# oresatt-batteries.net
KiCad netlist of a schematic drawn in EAGLE
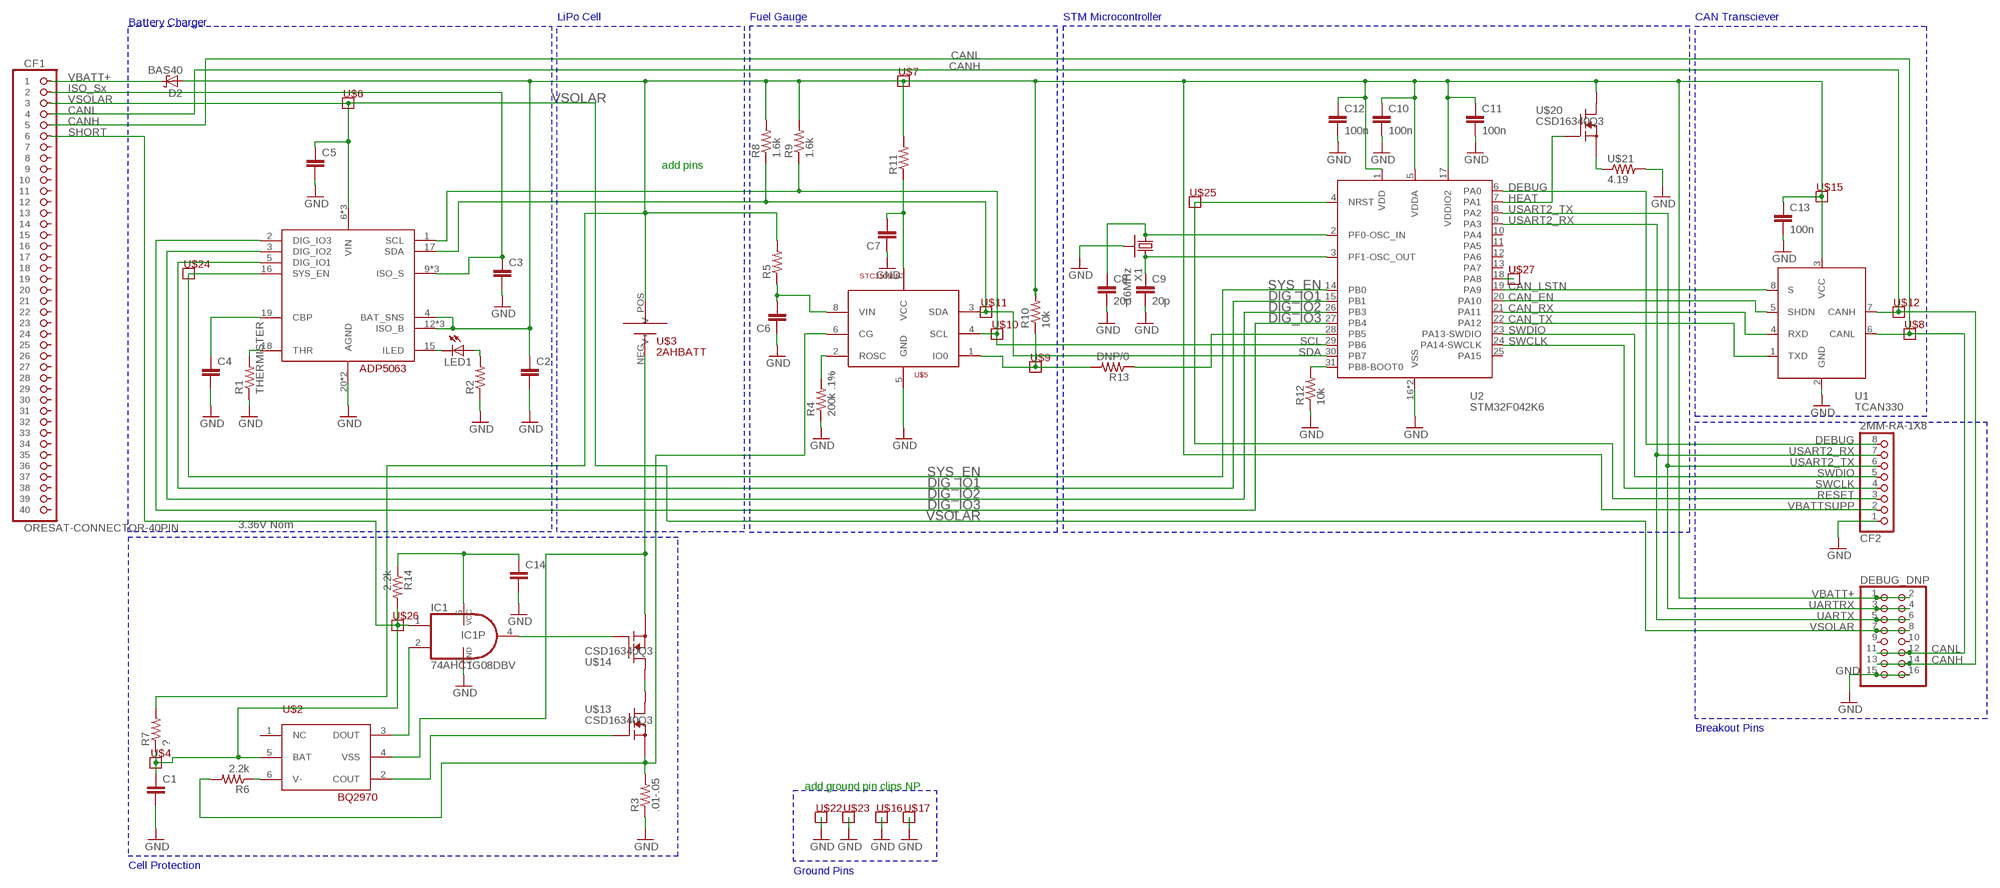
[diagram p0: schematic, sheet 1]

(export (version "E")
  (design (tool "Eeschema 10.0.6"))
  (components
    (comp (ref "C1")
      (value "C-EUC0603")
      (footprint "eagle-import:C0603")
      (libsource (lib "eagle-import") (part "C-EUC0603"))
    )
    (comp (ref "C2")
      (value "C-EUC0603")
      (footprint "eagle-import:C0603")
      (libsource (lib "eagle-import") (part "C-EUC0603"))
    )
    (comp (ref "C3")
      (value "C-EUC0603")
      (footprint "eagle-import:C0603")
      (libsource (lib "eagle-import") (part "C-EUC0603"))
    )
    (comp (ref "C4")
      (value "C-EUC0603")
      (footprint "eagle-import:C0603")
      (libsource (lib "eagle-import") (part "C-EUC0603"))
    )
    (comp (ref "C5")
      (value "C-EUC0603")
      (footprint "eagle-import:C0603")
      (libsource (lib "eagle-import") (part "C-EUC0603"))
    )
    (comp (ref "C6")
      (value "C-EUC0603")
      (footprint "eagle-import:C0603")
      (libsource (lib "eagle-import") (part "C-EUC0603"))
    )
    (comp (ref "C7")
      (value "C-EUC0603")
      (footprint "eagle-import:C0603")
      (libsource (lib "eagle-import") (part "C-EUC0603"))
    )
    (comp (ref "C8")
      (value "20p")
      (footprint "eagle-import:C0603")
      (libsource (lib "eagle-import") (part "C-EUC0603"))
    )
    (comp (ref "C9")
      (value "20p")
      (footprint "eagle-import:C0603")
      (libsource (lib "eagle-import") (part "C-EUC0603"))
    )
    (comp (ref "C10")
      (value "100n")
      (footprint "eagle-import:C0603")
      (libsource (lib "eagle-import") (part "C-EUC0603"))
    )
    (comp (ref "C11")
      (value "100n")
      (footprint "eagle-import:C0603")
      (libsource (lib "eagle-import") (part "C-EUC0603"))
    )
    (comp (ref "C12")
      (value "100n")
      (footprint "eagle-import:C0603")
      (libsource (lib "eagle-import") (part "C-EUC0603"))
    )
    (comp (ref "C13")
      (value "100n")
      (footprint "eagle-import:C0603")
      (libsource (lib "eagle-import") (part "C-EUC0603"))
    )
    (comp (ref "C14")
      (value "C-EUC0603")
      (footprint "eagle-import:C0603")
      (libsource (lib "eagle-import") (part "C-EUC0603"))
    )
    (comp (ref "CF1")
      (value "ORESAT-CONNECTOR-40PIN")
      (footprint "eagle-import:HARWIN-ARCHER-M50-3202045")
      (libsource (lib "eagle-import") (part "ORESAT-CONNECTOR-40PIN"))
    )
    (comp (ref "CF2")
      (value "2MM-RA-1X8")
      (footprint "eagle-import:CF-2MM-RA-1X8-PRECIDIP-831")
      (libsource (lib "eagle-import") (part "2MM-RA-1X8"))
    )
    (comp (ref "D2")
      (value "BAS40")
      (footprint "eagle-import:SOT23")
      (libsource (lib "eagle-import") (part "BAS40"))
    )
    (comp (ref "DEBUG_DNP")
      (value "PINHD-2X8")
      (footprint "eagle-import:2X08")
      (libsource (lib "eagle-import") (part "PINHD-2X8"))
    )
    (comp (ref "IC1")
      (value "74AHC1G08DBV")
      (footprint "eagle-import:SOT23-5")
      (libsource (lib "eagle-import") (part "741G08DBVAHC"))
    )
    (comp (ref "LED1")
      (value "LEDCHIPLED_0603")
      (footprint "eagle-import:CHIPLED_0603")
      (libsource (lib "eagle-import") (part "LEDCHIPLED_0603"))
    )
    (comp (ref "R1")
      (value "THERMISTER")
      (footprint "eagle-import:R0603")
      (libsource (lib "eagle-import") (part "R-US_R0603"))
    )
    (comp (ref "R2")
      (value "R-US_R0603")
      (footprint "eagle-import:R0603")
      (libsource (lib "eagle-import") (part "R-US_R0603"))
    )
    (comp (ref "R3")
      (value ".01-.05")
      (footprint "eagle-import:R0603")
      (libsource (lib "eagle-import") (part "R-US_R0603"))
    )
    (comp (ref "R4")
      (value "200k .1%")
      (footprint "eagle-import:R0603")
      (libsource (lib "eagle-import") (part "R-US_R0603"))
    )
    (comp (ref "R5")
      (value "R-US_R0603")
      (footprint "eagle-import:R0603")
      (libsource (lib "eagle-import") (part "R-US_R0603"))
    )
    (comp (ref "R6")
      (value "2.2k")
      (footprint "eagle-import:R0603")
      (libsource (lib "eagle-import") (part "R-US_R0603"))
    )
    (comp (ref "R7")
      (value "?")
      (footprint "eagle-import:R0603")
      (libsource (lib "eagle-import") (part "R-US_R0603"))
    )
    (comp (ref "R8")
      (value "1.6k")
      (footprint "eagle-import:R0603")
      (libsource (lib "eagle-import") (part "R-US_R0603"))
    )
    (comp (ref "R9")
      (value "1.6k")
      (footprint "eagle-import:R0603")
      (libsource (lib "eagle-import") (part "R-US_R0603"))
    )
    (comp (ref "R10")
      (value "10k")
      (footprint "eagle-import:R0603")
      (libsource (lib "eagle-import") (part "R-US_R0603"))
    )
    (comp (ref "R11")
      (value "R-US_R0603")
      (footprint "eagle-import:R0603")
      (libsource (lib "eagle-import") (part "R-US_R0603"))
    )
    (comp (ref "R12")
      (value "10k")
      (footprint "eagle-import:R0603")
      (libsource (lib "eagle-import") (part "R-US_R0603"))
    )
    (comp (ref "R13")
      (value "DNP/0")
      (footprint "eagle-import:R0603")
      (libsource (lib "eagle-import") (part "R-US_R0603"))
    )
    (comp (ref "R14")
      (value "2.2k")
      (footprint "eagle-import:R0603")
      (libsource (lib "eagle-import") (part "R-US_R0603"))
    )
    (comp (ref "U$1")
      (value "ADP5063")
      (footprint "eagle-import:20_4X4_VVTQ")
      (libsource (lib "eagle-import") (part "ADP5063"))
    )
    (comp (ref "U$2")
      (value "BQ2970")
      (footprint "eagle-import:PSOP6")
      (libsource (lib "eagle-import") (part "BQ2970"))
    )
    (comp (ref "U$3")
      (value "2AHBATT")
      (footprint "eagle-import:2AH_605060")
      (libsource (lib "eagle-import") (part "2AHBATT"))
    )
    (comp (ref "U$4")
      (value "TP")
      (footprint "eagle-import:2MM_TP")
      (libsource (lib "eagle-import") (part "TP"))
    )
    (comp (ref "U$5")
      (value "STC3100LST")
      (footprint "eagle-import:MINISO-8")
      (libsource (lib "eagle-import") (part "STC3100LST"))
    )
    (comp (ref "U$6")
      (value "TP")
      (footprint "eagle-import:2MM_TP")
      (libsource (lib "eagle-import") (part "TP"))
    )
    (comp (ref "U$7")
      (value "TP")
      (footprint "eagle-import:2MM_TP")
      (libsource (lib "eagle-import") (part "TP"))
    )
    (comp (ref "U$8")
      (value "TP")
      (footprint "eagle-import:2MM_TP")
      (libsource (lib "eagle-import") (part "TP"))
    )
    (comp (ref "U$9")
      (value "TP")
      (footprint "eagle-import:2MM_TP")
      (libsource (lib "eagle-import") (part "TP"))
    )
    (comp (ref "U$10")
      (value "TP")
      (footprint "eagle-import:2MM_TP")
      (libsource (lib "eagle-import") (part "TP"))
    )
    (comp (ref "U$11")
      (value "TP")
      (footprint "eagle-import:2MM_TP")
      (libsource (lib "eagle-import") (part "TP"))
    )
    (comp (ref "U$12")
      (value "TP")
      (footprint "eagle-import:2MM_TP")
      (libsource (lib "eagle-import") (part "TP"))
    )
    (comp (ref "U$13")
      (value "CSD16340Q3")
      (footprint "eagle-import:Q3")
      (libsource (lib "eagle-import") (part "CSD16340Q3"))
    )
    (comp (ref "U$14")
      (value "CSD16340Q3")
      (footprint "eagle-import:Q3")
      (libsource (lib "eagle-import") (part "CSD16340Q3"))
    )
    (comp (ref "U$15")
      (value "TP")
      (footprint "eagle-import:2MM_TP")
      (libsource (lib "eagle-import") (part "TP"))
    )
    (comp (ref "U$16")
      (value "TP")
      (footprint "eagle-import:2MM_TP")
      (libsource (lib "eagle-import") (part "TP"))
    )
    (comp (ref "U$17")
      (value "TP")
      (footprint "eagle-import:2MM_TP")
      (libsource (lib "eagle-import") (part "TP"))
    )
    (comp (ref "U$20")
      (value "CSD16340Q3")
      (footprint "eagle-import:Q3")
      (libsource (lib "eagle-import") (part "CSD16340Q3"))
    )
    (comp (ref "U$21")
      (value "4.19")
      (footprint "eagle-import:RES_HEATER")
      (libsource (lib "eagle-import") (part "RES_HEATER"))
    )
    (comp (ref "U$22")
      (value "TP")
      (footprint "eagle-import:2MM_TP")
      (libsource (lib "eagle-import") (part "TP"))
    )
    (comp (ref "U$23")
      (value "TP")
      (footprint "eagle-import:2MM_TP")
      (libsource (lib "eagle-import") (part "TP"))
    )
    (comp (ref "U$24")
      (value "TP")
      (footprint "eagle-import:2MM_TP")
      (libsource (lib "eagle-import") (part "TP"))
    )
    (comp (ref "U$25")
      (value "TP")
      (footprint "eagle-import:2MM_TP")
      (libsource (lib "eagle-import") (part "TP"))
    )
    (comp (ref "U$26")
      (value "TP")
      (footprint "eagle-import:2MM_TP")
      (libsource (lib "eagle-import") (part "TP"))
    )
    (comp (ref "U$27")
      (value "TP")
      (footprint "eagle-import:2MM_TP")
      (libsource (lib "eagle-import") (part "TP"))
    )
    (comp (ref "U1")
      (value "TCAN330")
      (footprint "eagle-import:SOT23-8_TI-DCN")
      (libsource (lib "eagle-import") (part "TCAN330"))
    )
    (comp (ref "U2")
      (value "STM32F042K6")
      (footprint "eagle-import:QFP32-7X7")
      (libsource (lib "eagle-import") (part "STM32F042K6"))
    )
    (comp (ref "X1")
      (value "16MHz")
      (footprint "eagle-import:CRYSTAL_2.5X2")
      (libsource (lib "eagle-import") (part "CRYSTAL-WITH-GND"))
    )
  )
  (nets
    (net (code "1") (name "GND") (class "Default")
      (node (ref "C1") (pin "2") (pinfunction "2_2") (pintype "passive"))
      (node (ref "C10") (pin "2") (pinfunction "2_2") (pintype "passive"))
      (node (ref "C11") (pin "2") (pinfunction "2_2") (pintype "passive"))
      (node (ref "C12") (pin "2") (pinfunction "2_2") (pintype "passive"))
      (node (ref "C13") (pin "2") (pinfunction "2_2") (pintype "passive"))
      (node (ref "C14") (pin "2") (pinfunction "2_2") (pintype "passive"))
      (node (ref "C2") (pin "2") (pinfunction "2_2") (pintype "passive"))
      (node (ref "C3") (pin "2") (pinfunction "2_2") (pintype "passive"))
      (node (ref "C4") (pin "2") (pinfunction "2_2") (pintype "passive"))
      (node (ref "C5") (pin "2") (pinfunction "2_2") (pintype "passive"))
      (node (ref "C6") (pin "1") (pinfunction "1_1") (pintype "passive"))
      (node (ref "C7") (pin "1") (pinfunction "1_1") (pintype "passive"))
      (node (ref "C8") (pin "2") (pinfunction "2_2") (pintype "passive"))
      (node (ref "C9") (pin "2") (pinfunction "2_2") (pintype "passive"))
      (node (ref "CF2") (pin "1") (pinfunction "1_1") (pintype "passive"))
      (node (ref "DEBUG_DNP") (pin "15") (pinfunction "15_15") (pintype "passive"))
      (node (ref "DEBUG_DNP") (pin "16") (pinfunction "16_16") (pintype "passive"))
      (node (ref "IC1") (pin "3") (pinfunction "GND_3") (pintype "power_in"))
      (node (ref "R1") (pin "1") (pinfunction "1_1") (pintype "passive"))
      (node (ref "R12") (pin "1") (pinfunction "1_1") (pintype "passive"))
      (node (ref "R2") (pin "1") (pinfunction "1_1") (pintype "passive"))
      (node (ref "R3") (pin "1") (pinfunction "1_1") (pintype "passive"))
      (node (ref "R4") (pin "1") (pinfunction "1_1") (pintype "passive"))
      (node (ref "U$1") (pin "20") (pinfunction "AGND_20") (pintype "bidirectional"))
      (node (ref "U$1") (pin "P$1") (pinfunction "AGND_P$1") (pintype "bidirectional"))
      (node (ref "U$21") (pin "V-") (pinfunction "2_V-") (pintype "passive"))
      (node (ref "U$5") (pin "5") (pinfunction "GND_5") (pintype "bidirectional"))
      (node (ref "U1") (pin "2") (pinfunction "GND_2") (pintype "power_in"))
      (node (ref "U2") (pin "16") (pinfunction "VSS_16") (pintype "power_in"))
      (node (ref "U2") (pin "32") (pinfunction "VSS_32") (pintype "power_in"))
      (node (ref "X1") (pin "2") (pinfunction "SHIELD_2") (pintype "power_in"))
      (node (ref "X1") (pin "4") (pinfunction "SHIELD_4") (pintype "power_in"))
    )
    (net (code "2") (name "Net-(CF1-1)") (class "Default")
      (node (ref "CF1") (pin "P$1") (pinfunction "1_P$1") (pintype "passive"))
      (node (ref "D2") (pin "3") (pinfunction "C_3") (pintype "passive"))
    )
    (net (code "3") (name "Net-(CF1-2)") (class "Default")
      (node (ref "C3") (pin "1") (pinfunction "1_1") (pintype "passive"))
      (node (ref "CF1") (pin "P$2") (pinfunction "2_P$2") (pintype "passive"))
      (node (ref "U$1") (pin "10") (pinfunction "ISO_S_10") (pintype "bidirectional"))
      (node (ref "U$1") (pin "11") (pinfunction "ISO_S_11") (pintype "bidirectional"))
      (node (ref "U$1") (pin "9") (pinfunction "ISO_S_9") (pintype "bidirectional"))
    )
    (net (code "4") (name "Net-(CF1-3)") (class "Default")
      (node (ref "C5") (pin "1") (pinfunction "1_1") (pintype "passive"))
      (node (ref "CF1") (pin "P$3") (pinfunction "3_P$3") (pintype "passive"))
      (node (ref "DEBUG_DNP") (pin "7") (pinfunction "7_7") (pintype "passive"))
      (node (ref "DEBUG_DNP") (pin "8") (pinfunction "8_8") (pintype "passive"))
      (node (ref "U$1") (pin "6") (pinfunction "VIN_6") (pintype "bidirectional"))
      (node (ref "U$1") (pin "7") (pinfunction "VIN_7") (pintype "bidirectional"))
      (node (ref "U$1") (pin "8") (pinfunction "VIN_8") (pintype "bidirectional"))
    )
    (net (code "5") (name "Net-(CF1-4)") (class "Default")
      (node (ref "CF1") (pin "P$4") (pinfunction "4_P$4") (pintype "passive"))
      (node (ref "DEBUG_DNP") (pin "13") (pinfunction "13_13") (pintype "passive"))
      (node (ref "DEBUG_DNP") (pin "14") (pinfunction "14_14") (pintype "passive"))
      (node (ref "U1") (pin "7") (pinfunction "CANH_7") (pintype "bidirectional"))
    )
    (net (code "6") (name "Net-(CF1-5)") (class "Default")
      (node (ref "CF1") (pin "P$5") (pinfunction "5_P$5") (pintype "passive"))
      (node (ref "DEBUG_DNP") (pin "11") (pinfunction "11_11") (pintype "passive"))
      (node (ref "DEBUG_DNP") (pin "12") (pinfunction "12_12") (pintype "passive"))
      (node (ref "U1") (pin "6") (pinfunction "CANL_6") (pintype "bidirectional"))
    )
    (net (code "7") (name "Net-(CF1-6)") (class "Default")
      (node (ref "C1") (pin "1") (pinfunction "1_1") (pintype "passive"))
      (node (ref "CF1") (pin "P$6") (pinfunction "6_P$6") (pintype "passive"))
      (node (ref "IC1") (pin "1") (pinfunction "I0_1") (pintype "input"))
      (node (ref "R14") (pin "2") (pinfunction "2_2") (pintype "passive"))
      (node (ref "R7") (pin "1") (pinfunction "1_1") (pintype "passive"))
      (node (ref "U$2") (pin "5") (pinfunction "BAT_5") (pintype "bidirectional"))
    )
    (net (code "8") (name "Net-(D2-A)") (class "Default")
      (node (ref "C10") (pin "1") (pinfunction "1_1") (pintype "passive"))
      (node (ref "C11") (pin "1") (pinfunction "1_1") (pintype "passive"))
      (node (ref "C12") (pin "1") (pinfunction "1_1") (pintype "passive"))
      (node (ref "C13") (pin "1") (pinfunction "1_1") (pintype "passive"))
      (node (ref "C2") (pin "1") (pinfunction "1_1") (pintype "passive"))
      (node (ref "CF2") (pin "2") (pinfunction "2_2") (pintype "passive"))
      (node (ref "D2") (pin "1") (pinfunction "A_1") (pintype "passive"))
      (node (ref "DEBUG_DNP") (pin "1") (pinfunction "1_1") (pintype "passive"))
      (node (ref "DEBUG_DNP") (pin "2") (pinfunction "2_2") (pintype "passive"))
      (node (ref "R10") (pin "2") (pinfunction "2_2") (pintype "passive"))
      (node (ref "R11") (pin "2") (pinfunction "2_2") (pintype "passive"))
      (node (ref "R5") (pin "2") (pinfunction "2_2") (pintype "passive"))
      (node (ref "R7") (pin "2") (pinfunction "2_2") (pintype "passive"))
      (node (ref "R8") (pin "2") (pinfunction "2_2") (pintype "passive"))
      (node (ref "R9") (pin "2") (pinfunction "2_2") (pintype "passive"))
      (node (ref "U$1") (pin "12") (pinfunction "ISO_B_12") (pintype "bidirectional"))
      (node (ref "U$1") (pin "13") (pinfunction "ISO_B_13") (pintype "bidirectional"))
      (node (ref "U$1") (pin "14") (pinfunction "ISO_B_14") (pintype "bidirectional"))
      (node (ref "U$1") (pin "4") (pinfunction "BAT_SNS_4") (pintype "bidirectional"))
      (node (ref "U$20") (pin "P$5") (pinfunction "D_P$5") (pintype "passive"))
      (node (ref "U$20") (pin "P$6") (pinfunction "D_P$6") (pintype "passive"))
      (node (ref "U$20") (pin "P$7") (pinfunction "D_P$7") (pintype "passive"))
      (node (ref "U$20") (pin "P$8") (pinfunction "D_P$8") (pintype "passive"))
      (node (ref "U$20") (pin "P$9") (pinfunction "D_P$9") (pintype "passive"))
      (node (ref "U$3") (pin "POS") (pinfunction "V+_POS") (pintype "bidirectional"))
      (node (ref "U1") (pin "3") (pinfunction "VCC_3") (pintype "power_in"))
      (node (ref "U2") (pin "1") (pinfunction "VDD_1") (pintype "power_in"))
      (node (ref "U2") (pin "17") (pinfunction "VDDIO2_17") (pintype "power_in"))
      (node (ref "U2") (pin "5") (pinfunction "VDDA_5") (pintype "power_in"))
    )
    (net (code "9") (name "Net-(IC1A-I1)") (class "Default")
      (node (ref "IC1") (pin "2") (pinfunction "I1_2") (pintype "input"))
      (node (ref "U$2") (pin "3") (pinfunction "DOUT_3") (pintype "bidirectional"))
    )
    (net (code "10") (name "Net-(IC1A-O)") (class "Default")
      (node (ref "IC1") (pin "4") (pinfunction "O_4") (pintype "output"))
      (node (ref "U$14") (pin "P$4") (pinfunction "G_P$4") (pintype "passive"))
    )
    (net (code "11") (name "Net-(IC1B-VCC)") (class "Default")
      (node (ref "C14") (pin "1") (pinfunction "1_1") (pintype "passive"))
      (node (ref "IC1") (pin "5") (pinfunction "VCC_5") (pintype "power_in"))
      (node (ref "R14") (pin "1") (pinfunction "1_1") (pintype "passive"))
    )
    (net (code "12") (name "Net-(LED1-PadA)") (class "Default")
      (node (ref "LED1") (pin "A") (pinfunction "A_A") (pintype "passive"))
      (node (ref "R2") (pin "2") (pinfunction "2_2") (pintype "passive"))
    )
    (net (code "13") (name "Net-(U$1-CBP)") (class "Default")
      (node (ref "C4") (pin "1") (pinfunction "1_1") (pintype "passive"))
      (node (ref "U$1") (pin "19") (pinfunction "CBP_19") (pintype "bidirectional"))
    )
    (net (code "14") (name "Net-(U$1-DIG_IO1)") (class "Default")
      (node (ref "U$1") (pin "5") (pinfunction "DIG_IO1_5") (pintype "bidirectional"))
      (node (ref "U2") (pin "15") (pinfunction "PB1_15") (pintype "bidirectional"))
    )
    (net (code "15") (name "Net-(U$1-DIG_IO2)") (class "Default")
      (node (ref "U$1") (pin "3") (pinfunction "DIG_IO2_3") (pintype "bidirectional"))
      (node (ref "U2") (pin "26") (pinfunction "PB3_26") (pintype "bidirectional"))
    )
    (net (code "16") (name "Net-(U$1-DIG_IO3)") (class "Default")
      (node (ref "U$1") (pin "2") (pinfunction "DIG_IO3_2") (pintype "bidirectional"))
      (node (ref "U2") (pin "27") (pinfunction "PB4_27") (pintype "bidirectional"))
    )
    (net (code "17") (name "Net-(U$1-ILED)") (class "Default")
      (node (ref "LED1") (pin "C") (pinfunction "C_C") (pintype "passive"))
      (node (ref "U$1") (pin "15") (pinfunction "ILED_15") (pintype "bidirectional"))
    )
    (net (code "18") (name "Net-(U$1-SCL)") (class "Default")
      (node (ref "R9") (pin "1") (pinfunction "1_1") (pintype "passive"))
      (node (ref "U$1") (pin "1") (pinfunction "SCL_1") (pintype "bidirectional"))
      (node (ref "U$5") (pin "4") (pinfunction "SCL_4") (pintype "bidirectional"))
      (node (ref "U2") (pin "29") (pinfunction "PB6_29") (pintype "bidirectional"))
    )
    (net (code "19") (name "Net-(U$1-SDA)") (class "Default")
      (node (ref "R8") (pin "1") (pinfunction "1_1") (pintype "passive"))
      (node (ref "U$1") (pin "17") (pinfunction "SDA_17") (pintype "bidirectional"))
      (node (ref "U$5") (pin "3") (pinfunction "SDA_3") (pintype "bidirectional"))
      (node (ref "U2") (pin "30") (pinfunction "PB7_30") (pintype "bidirectional"))
    )
    (net (code "20") (name "Net-(U$1-SYS_EN)") (class "Default")
      (node (ref "U$1") (pin "16") (pinfunction "SYS_EN_16") (pintype "bidirectional"))
      (node (ref "U2") (pin "14") (pinfunction "PB0_14") (pintype "bidirectional"))
    )
    (net (code "21") (name "Net-(U$1-THR)") (class "Default")
      (node (ref "R1") (pin "2") (pinfunction "2_2") (pintype "passive"))
      (node (ref "U$1") (pin "18") (pinfunction "THR_18") (pintype "bidirectional"))
    )
    (net (code "22") (name "Net-(U$2-V-)") (class "Default")
      (node (ref "R6") (pin "1") (pinfunction "1_1") (pintype "passive"))
      (node (ref "U$2") (pin "6") (pinfunction "V-_6") (pintype "bidirectional"))
    )
    (net (code "23") (name "Net-(U$2-VSS)") (class "Default")
      (node (ref "U$14") (pin "P$1") (pinfunction "S_P$1") (pintype "passive"))
      (node (ref "U$14") (pin "P$2") (pinfunction "S_P$2") (pintype "passive"))
      (node (ref "U$14") (pin "P$3") (pinfunction "S_P$3") (pintype "passive"))
      (node (ref "U$2") (pin "4") (pinfunction "VSS_4") (pintype "bidirectional"))
      (node (ref "U$3") (pin "NEG") (pinfunction "V-_NEG") (pintype "bidirectional"))
    )
    (net (code "24") (name "Net-(U$5-CG)") (class "Default")
      (node (ref "R3") (pin "2") (pinfunction "2_2") (pintype "passive"))
      (node (ref "R6") (pin "2") (pinfunction "2_2") (pintype "passive"))
      (node (ref "U$13") (pin "P$1") (pinfunction "S_P$1") (pintype "passive"))
      (node (ref "U$13") (pin "P$2") (pinfunction "S_P$2") (pintype "passive"))
      (node (ref "U$13") (pin "P$3") (pinfunction "S_P$3") (pintype "passive"))
      (node (ref "U$5") (pin "6") (pinfunction "CG_6") (pintype "bidirectional"))
    )
    (net (code "25") (name "Net-(U$5-IO0)") (class "Default")
      (node (ref "R10") (pin "1") (pinfunction "1_1") (pintype "passive"))
      (node (ref "R13") (pin "2") (pinfunction "2_2") (pintype "passive"))
      (node (ref "U$5") (pin "1") (pinfunction "IO0_1") (pintype "bidirectional"))
    )
    (net (code "26") (name "Net-(U$5-ROSC)") (class "Default")
      (node (ref "R4") (pin "2") (pinfunction "2_2") (pintype "passive"))
      (node (ref "U$5") (pin "2") (pinfunction "ROSC_2") (pintype "bidirectional"))
    )
    (net (code "27") (name "Net-(U$5-VCC)") (class "Default")
      (node (ref "C7") (pin "2") (pinfunction "2_2") (pintype "passive"))
      (node (ref "R11") (pin "1") (pinfunction "1_1") (pintype "passive"))
      (node (ref "U$5") (pin "7") (pinfunction "VCC_7") (pintype "bidirectional"))
    )
    (net (code "28") (name "Net-(U$5-VIN)") (class "Default")
      (node (ref "C6") (pin "2") (pinfunction "2_2") (pintype "passive"))
      (node (ref "R5") (pin "1") (pinfunction "1_1") (pintype "passive"))
      (node (ref "U$5") (pin "8") (pinfunction "VIN_8") (pintype "bidirectional"))
    )
    (net (code "29") (name "Net-(U$13-D-PadP$5)") (class "Default")
      (node (ref "U$13") (pin "P$5") (pinfunction "D_P$5") (pintype "passive"))
      (node (ref "U$13") (pin "P$6") (pinfunction "D_P$6") (pintype "passive"))
      (node (ref "U$13") (pin "P$7") (pinfunction "D_P$7") (pintype "passive"))
      (node (ref "U$13") (pin "P$8") (pinfunction "D_P$8") (pintype "passive"))
      (node (ref "U$13") (pin "P$9") (pinfunction "D_P$9") (pintype "passive"))
      (node (ref "U$14") (pin "P$5") (pinfunction "D_P$5") (pintype "passive"))
      (node (ref "U$14") (pin "P$6") (pinfunction "D_P$6") (pintype "passive"))
      (node (ref "U$14") (pin "P$7") (pinfunction "D_P$7") (pintype "passive"))
      (node (ref "U$14") (pin "P$8") (pinfunction "D_P$8") (pintype "passive"))
      (node (ref "U$14") (pin "P$9") (pinfunction "D_P$9") (pintype "passive"))
    )
    (net (code "30") (name "Net-(U$13-G)") (class "Default")
      (node (ref "U$13") (pin "P$4") (pinfunction "G_P$4") (pintype "passive"))
      (node (ref "U$2") (pin "2") (pinfunction "COUT_2") (pintype "bidirectional"))
    )
    (net (code "31") (name "Net-(U$20-G)") (class "Default")
      (node (ref "U$20") (pin "P$4") (pinfunction "G_P$4") (pintype "passive"))
      (node (ref "U2") (pin "7") (pinfunction "PA1_7") (pintype "bidirectional"))
    )
    (net (code "32") (name "Net-(U$21-1)") (class "Default")
      (node (ref "U$20") (pin "P$1") (pinfunction "S_P$1") (pintype "passive"))
      (node (ref "U$20") (pin "P$2") (pinfunction "S_P$2") (pintype "passive"))
      (node (ref "U$20") (pin "P$3") (pinfunction "S_P$3") (pintype "passive"))
      (node (ref "U$21") (pin "V+") (pinfunction "1_V+") (pintype "passive"))
    )
    (net (code "33") (name "Net-(U1-RXD)") (class "Default")
      (node (ref "U1") (pin "4") (pinfunction "RXD_4") (pintype "output"))
      (node (ref "U2") (pin "21") (pinfunction "PA11_21") (pintype "bidirectional"))
    )
    (net (code "34") (name "Net-(U1-S)") (class "Default")
      (node (ref "U1") (pin "8") (pinfunction "S_8") (pintype "input"))
      (node (ref "U2") (pin "19") (pinfunction "PA9_19") (pintype "bidirectional"))
    )
    (net (code "35") (name "Net-(U1-SHDN)") (class "Default")
      (node (ref "U1") (pin "5") (pinfunction "SHDN_5") (pintype "input"))
      (node (ref "U2") (pin "20") (pinfunction "PA10_20") (pintype "bidirectional"))
    )
    (net (code "36") (name "Net-(U1-TXD)") (class "Default")
      (node (ref "U1") (pin "1") (pinfunction "TXD_1") (pintype "input"))
      (node (ref "U2") (pin "22") (pinfunction "PA12_22") (pintype "bidirectional"))
    )
    (net (code "37") (name "Net-(U2-NRST)") (class "Default")
      (node (ref "CF2") (pin "3") (pinfunction "3_3") (pintype "passive"))
      (node (ref "U2") (pin "4") (pinfunction "NRST_4") (pintype "bidirectional"))
    )
    (net (code "38") (name "Net-(U2-PA0)") (class "Default")
      (node (ref "CF2") (pin "8") (pinfunction "8_8") (pintype "passive"))
      (node (ref "U2") (pin "6") (pinfunction "PA0_6") (pintype "bidirectional"))
    )
    (net (code "39") (name "Net-(U2-PA2)") (class "Default")
      (node (ref "CF2") (pin "6") (pinfunction "6_6") (pintype "passive"))
      (node (ref "DEBUG_DNP") (pin "3") (pinfunction "3_3") (pintype "passive"))
      (node (ref "DEBUG_DNP") (pin "4") (pinfunction "4_4") (pintype "passive"))
      (node (ref "U2") (pin "8") (pinfunction "PA2_8") (pintype "bidirectional"))
    )
    (net (code "40") (name "Net-(U2-PA3)") (class "Default")
      (node (ref "CF2") (pin "7") (pinfunction "7_7") (pintype "passive"))
      (node (ref "DEBUG_DNP") (pin "5") (pinfunction "5_5") (pintype "passive"))
      (node (ref "DEBUG_DNP") (pin "6") (pinfunction "6_6") (pintype "passive"))
      (node (ref "U2") (pin "9") (pinfunction "PA3_9") (pintype "bidirectional"))
    )
    (net (code "41") (name "Net-(U2-PA13-SWDIO)") (class "Default")
      (node (ref "CF2") (pin "5") (pinfunction "5_5") (pintype "passive"))
      (node (ref "U2") (pin "23") (pinfunction "PA13-SWDIO_23") (pintype "bidirectional"))
    )
    (net (code "42") (name "Net-(U2-PA14-SWCLK)") (class "Default")
      (node (ref "CF2") (pin "4") (pinfunction "4_4") (pintype "passive"))
      (node (ref "U2") (pin "24") (pinfunction "PA14-SWCLK_24") (pintype "bidirectional"))
    )
    (net (code "43") (name "Net-(U2-PB5)") (class "Default")
      (node (ref "R13") (pin "1") (pinfunction "1_1") (pintype "passive"))
      (node (ref "U2") (pin "28") (pinfunction "PB5_28") (pintype "bidirectional"))
    )
    (net (code "44") (name "Net-(U2-PB8-BOOT0)") (class "Default")
      (node (ref "R12") (pin "2") (pinfunction "2_2") (pintype "passive"))
      (node (ref "U2") (pin "31") (pinfunction "PB8-BOOT0_31") (pintype "bidirectional"))
    )
    (net (code "45") (name "Net-(U2-PF0-OSC_IN)") (class "Default")
      (node (ref "C8") (pin "1") (pinfunction "1_1") (pintype "passive"))
      (node (ref "U2") (pin "2") (pinfunction "PF0-OSC_IN_2") (pintype "bidirectional"))
      (node (ref "X1") (pin "1") (pinfunction "1_1") (pintype "passive"))
    )
    (net (code "46") (name "Net-(U2-PF1-OSC_OUT)") (class "Default")
      (node (ref "C9") (pin "1") (pinfunction "1_1") (pintype "passive"))
      (node (ref "U2") (pin "3") (pinfunction "PF1-OSC_OUT_3") (pintype "bidirectional"))
      (node (ref "X1") (pin "3") (pinfunction "2_3") (pintype "passive"))
    )
    (net (code "47") (name "unconnected-(CF1-7-PadP$7)") (class "Default")
      (node (ref "CF1") (pin "P$7") (pinfunction "7_P$7") (pintype "passive"))
    )
    (net (code "48") (name "unconnected-(CF1-8-PadP$8)") (class "Default")
      (node (ref "CF1") (pin "P$8") (pinfunction "8_P$8") (pintype "passive"))
    )
    (net (code "49") (name "unconnected-(CF1-9-PadP$9)") (class "Default")
      (node (ref "CF1") (pin "P$9") (pinfunction "9_P$9") (pintype "passive"))
    )
    (net (code "50") (name "unconnected-(CF1-10-PadP$10)") (class "Default")
      (node (ref "CF1") (pin "P$10") (pinfunction "10_P$10") (pintype "passive"))
    )
    (net (code "51") (name "unconnected-(CF1-11-PadP$11)") (class "Default")
      (node (ref "CF1") (pin "P$11") (pinfunction "11_P$11") (pintype "passive"))
    )
    (net (code "52") (name "unconnected-(CF1-12-PadP$12)") (class "Default")
      (node (ref "CF1") (pin "P$12") (pinfunction "12_P$12") (pintype "passive"))
    )
    (net (code "53") (name "unconnected-(CF1-13-PadP$13)") (class "Default")
      (node (ref "CF1") (pin "P$13") (pinfunction "13_P$13") (pintype "passive"))
    )
    (net (code "54") (name "unconnected-(CF1-14-PadP$14)") (class "Default")
      (node (ref "CF1") (pin "P$14") (pinfunction "14_P$14") (pintype "passive"))
    )
    (net (code "55") (name "unconnected-(CF1-15-PadP$15)") (class "Default")
      (node (ref "CF1") (pin "P$15") (pinfunction "15_P$15") (pintype "passive"))
    )
    (net (code "56") (name "unconnected-(CF1-16-PadP$16)") (class "Default")
      (node (ref "CF1") (pin "P$16") (pinfunction "16_P$16") (pintype "passive"))
    )
    (net (code "57") (name "unconnected-(CF1-17-PadP$17)") (class "Default")
      (node (ref "CF1") (pin "P$17") (pinfunction "17_P$17") (pintype "passive"))
    )
    (net (code "58") (name "unconnected-(CF1-18-PadP$18)") (class "Default")
      (node (ref "CF1") (pin "P$18") (pinfunction "18_P$18") (pintype "passive"))
    )
    (net (code "59") (name "unconnected-(CF1-19-PadP$19)") (class "Default")
      (node (ref "CF1") (pin "P$19") (pinfunction "19_P$19") (pintype "passive"))
    )
    (net (code "60") (name "unconnected-(CF1-20-PadP$20)") (class "Default")
      (node (ref "CF1") (pin "P$20") (pinfunction "20_P$20") (pintype "passive"))
    )
    (net (code "61") (name "unconnected-(CF1-21-PadP$21)") (class "Default")
      (node (ref "CF1") (pin "P$21") (pinfunction "21_P$21") (pintype "passive"))
    )
    (net (code "62") (name "unconnected-(CF1-22-PadP$22)") (class "Default")
      (node (ref "CF1") (pin "P$22") (pinfunction "22_P$22") (pintype "passive"))
    )
    (net (code "63") (name "unconnected-(CF1-23-PadP$23)") (class "Default")
      (node (ref "CF1") (pin "P$23") (pinfunction "23_P$23") (pintype "passive"))
    )
    (net (code "64") (name "unconnected-(CF1-24-PadP$24)") (class "Default")
      (node (ref "CF1") (pin "P$24") (pinfunction "24_P$24") (pintype "passive"))
    )
    (net (code "65") (name "unconnected-(CF1-25-PadP$25)") (class "Default")
      (node (ref "CF1") (pin "P$25") (pinfunction "25_P$25") (pintype "passive"))
    )
    (net (code "66") (name "unconnected-(CF1-26-PadP$26)") (class "Default")
      (node (ref "CF1") (pin "P$26") (pinfunction "26_P$26") (pintype "passive"))
    )
    (net (code "67") (name "unconnected-(CF1-27-PadP$27)") (class "Default")
      (node (ref "CF1") (pin "P$27") (pinfunction "27_P$27") (pintype "passive"))
    )
    (net (code "68") (name "unconnected-(CF1-28-PadP$28)") (class "Default")
      (node (ref "CF1") (pin "P$28") (pinfunction "28_P$28") (pintype "passive"))
    )
    (net (code "69") (name "unconnected-(CF1-29-PadP$29)") (class "Default")
      (node (ref "CF1") (pin "P$29") (pinfunction "29_P$29") (pintype "passive"))
    )
    (net (code "70") (name "unconnected-(CF1-30-PadP$30)") (class "Default")
      (node (ref "CF1") (pin "P$30") (pinfunction "30_P$30") (pintype "passive"))
    )
    (net (code "71") (name "unconnected-(CF1-31-PadP$31)") (class "Default")
      (node (ref "CF1") (pin "P$31") (pinfunction "31_P$31") (pintype "passive"))
    )
    (net (code "72") (name "unconnected-(CF1-32-PadP$32)") (class "Default")
      (node (ref "CF1") (pin "P$32") (pinfunction "32_P$32") (pintype "passive"))
    )
    (net (code "73") (name "unconnected-(CF1-33-PadP$33)") (class "Default")
      (node (ref "CF1") (pin "P$33") (pinfunction "33_P$33") (pintype "passive"))
    )
    (net (code "74") (name "unconnected-(CF1-34-PadP$34)") (class "Default")
      (node (ref "CF1") (pin "P$34") (pinfunction "34_P$34") (pintype "passive"))
    )
    (net (code "75") (name "unconnected-(CF1-35-PadP$35)") (class "Default")
      (node (ref "CF1") (pin "P$35") (pinfunction "35_P$35") (pintype "passive"))
    )
    (net (code "76") (name "unconnected-(CF1-36-PadP$36)") (class "Default")
      (node (ref "CF1") (pin "P$36") (pinfunction "36_P$36") (pintype "passive"))
    )
    (net (code "77") (name "unconnected-(CF1-37-PadP$37)") (class "Default")
      (node (ref "CF1") (pin "P$37") (pinfunction "37_P$37") (pintype "passive"))
    )
    (net (code "78") (name "unconnected-(CF1-38-PadP$38)") (class "Default")
      (node (ref "CF1") (pin "P$38") (pinfunction "38_P$38") (pintype "passive"))
    )
    (net (code "79") (name "unconnected-(CF1-39-PadP$39)") (class "Default")
      (node (ref "CF1") (pin "P$39") (pinfunction "39_P$39") (pintype "passive"))
    )
    (net (code "80") (name "unconnected-(CF1-40-PadP$40)") (class "Default")
      (node (ref "CF1") (pin "P$40") (pinfunction "40_P$40") (pintype "passive"))
    )
    (net (code "81") (name "unconnected-(DEBUG_DNP-Pad9)") (class "Default")
      (node (ref "DEBUG_DNP") (pin "9") (pinfunction "9_9") (pintype "passive"))
    )
    (net (code "82") (name "unconnected-(DEBUG_DNP-Pad10)") (class "Default")
      (node (ref "DEBUG_DNP") (pin "10") (pinfunction "10_10") (pintype "passive"))
    )
    (net (code "83") (name "unconnected-(U$2-NC-Pad1)") (class "Default")
      (node (ref "U$2") (pin "1") (pinfunction "NC_1") (pintype "bidirectional"))
    )
    (net (code "84") (name "unconnected-(U2-PA4-Pad10)") (class "Default")
      (node (ref "U2") (pin "10") (pinfunction "PA4_10") (pintype "bidirectional"))
    )
    (net (code "85") (name "unconnected-(U2-PA5-Pad11)") (class "Default")
      (node (ref "U2") (pin "11") (pinfunction "PA5_11") (pintype "bidirectional"))
    )
    (net (code "86") (name "unconnected-(U2-PA6-Pad12)") (class "Default")
      (node (ref "U2") (pin "12") (pinfunction "PA6_12") (pintype "bidirectional"))
    )
    (net (code "87") (name "unconnected-(U2-PA7-Pad13)") (class "Default")
      (node (ref "U2") (pin "13") (pinfunction "PA7_13") (pintype "bidirectional"))
    )
    (net (code "88") (name "unconnected-(U2-PA8-Pad18)") (class "Default")
      (node (ref "U2") (pin "18") (pinfunction "PA8_18") (pintype "bidirectional"))
    )
    (net (code "89") (name "unconnected-(U2-PA15-Pad25)") (class "Default")
      (node (ref "U2") (pin "25") (pinfunction "PA15_25") (pintype "bidirectional"))
    )
  )
)
